# machcauH.net
KiCad netlist of a schematic drawn in Altium Designer
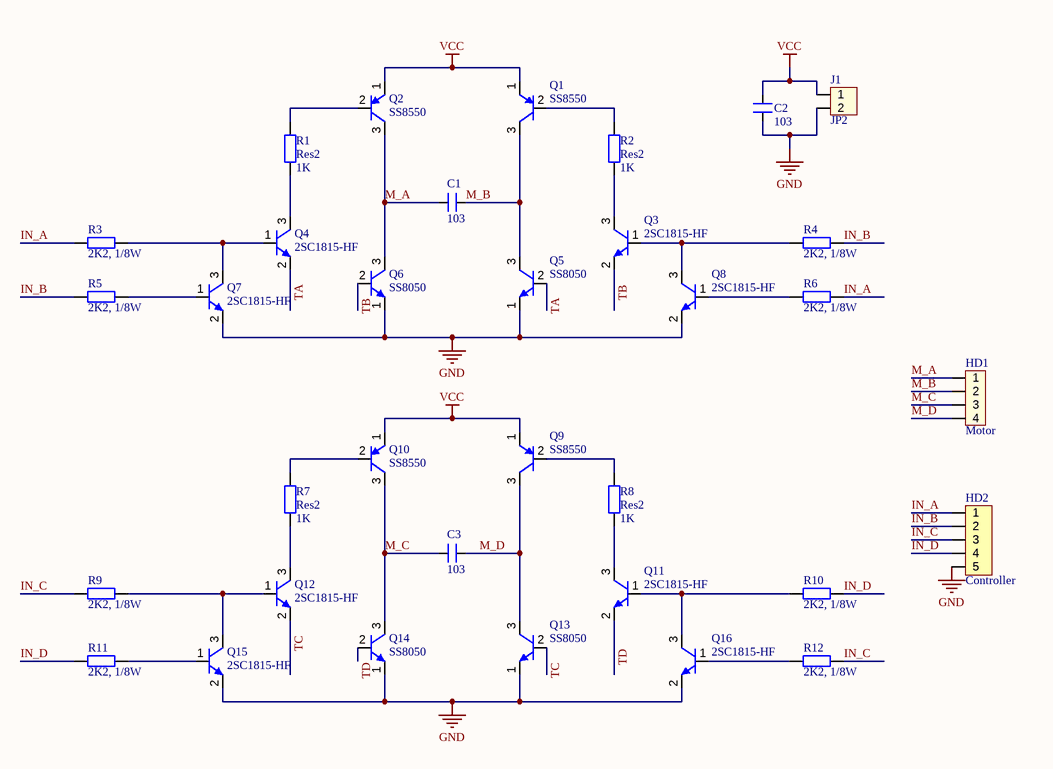
[diagram p0: machcauH.SchDoc]

(export (version "E")
  (design (tool "Eeschema 10.0.6"))
  (components
    (comp (ref "C1")
      (value "103")
      (footprint "CN1.5")
      (description "Cap np 682pF => 104pF")
      (libsource (lib "lpson") (part "CN1.5"))
    )
    (comp (ref "C2")
      (value "103")
      (footprint "CN1.5")
      (description "Cap np 682pF => 104pF")
      (libsource (lib "lpson") (part "CN1.5"))
    )
    (comp (ref "C3")
      (value "103")
      (footprint "CN1.5")
      (description "Cap np 682pF => 104pF")
      (libsource (lib "lpson") (part "CN1.5"))
    )
    (comp (ref "HD1")
      (value "Motor")
      (footprint "Header_4")
      (description "Header 4")
      (libsource (lib "lpson") (part "Header4"))
    )
    (comp (ref "HD2")
      (value "Controller")
      (footprint "HDR5")
      (description "Header IDC, 5 x 1 Pin Vertical 2.54mm Pitch (Non-Boxed, Male)")
      (fields
        (field (name "MANUFACTURER") "Würth Elektronik eiSos GmbH")
        (field (name "PARTNO") "613002143121")
        (field (name "CREATED BY") "Karrer Zheng")
      )
      (libsource (lib "My Library") (part "Header5"))
    )
    (comp (ref "J1")
      (value "JP2")
      (footprint "CON2")
      (description "Connector 2")
      (libsource (lib "lpson") (part "Con2"))
    )
    (comp (ref "Q1")
      (value "SS8550")
      (footprint "SS8550")
      (description "Trans PNP -25V -1.5A TO-92")
      (libsource (lib "lpson") (part "SS8550"))
    )
    (comp (ref "Q2")
      (value "SS8550")
      (footprint "SS8550")
      (description "Trans PNP -25V -1.5A TO-92")
      (libsource (lib "lpson") (part "SS8550"))
    )
    (comp (ref "Q3")
      (value "2SC1815-HF")
      (footprint "2SC1815-HF")
      (description "Trans NPN 50V 150mA SOT-23")
      (libsource (lib "lpson") (part "2SC1815-HF"))
    )
    (comp (ref "Q4")
      (value "2SC1815-HF")
      (footprint "2SC1815-HF")
      (description "Trans NPN 50V 150mA SOT-23")
      (libsource (lib "lpson") (part "2SC1815-HF"))
    )
    (comp (ref "Q5")
      (value "SS8050")
      (footprint "SS8050")
      (description "Trans NPN 25V 1.5A TO-92")
      (libsource (lib "lpson") (part "SS8050"))
    )
    (comp (ref "Q6")
      (value "SS8050")
      (footprint "SS8050")
      (description "Trans NPN 25V 1.5A TO-92")
      (libsource (lib "lpson") (part "SS8050"))
    )
    (comp (ref "Q7")
      (value "2SC1815-HF")
      (footprint "2SC1815-HF")
      (description "Trans NPN 50V 150mA SOT-23")
      (libsource (lib "lpson") (part "2SC1815-HF"))
    )
    (comp (ref "Q8")
      (value "2SC1815-HF")
      (footprint "2SC1815-HF")
      (description "Trans NPN 50V 150mA SOT-23")
      (libsource (lib "lpson") (part "2SC1815-HF"))
    )
    (comp (ref "Q9")
      (value "SS8550")
      (footprint "SS8550")
      (description "Trans PNP -25V -1.5A TO-92")
      (libsource (lib "lpson") (part "SS8550"))
    )
    (comp (ref "Q10")
      (value "SS8550")
      (footprint "SS8550")
      (description "Trans PNP -25V -1.5A TO-92")
      (libsource (lib "lpson") (part "SS8550"))
    )
    (comp (ref "Q11")
      (value "2SC1815-HF")
      (footprint "2SC1815-HF")
      (description "Trans NPN 50V 150mA SOT-23")
      (libsource (lib "lpson") (part "2SC1815-HF"))
    )
    (comp (ref "Q12")
      (value "2SC1815-HF")
      (footprint "2SC1815-HF")
      (description "Trans NPN 50V 150mA SOT-23")
      (libsource (lib "lpson") (part "2SC1815-HF"))
    )
    (comp (ref "Q13")
      (value "SS8050")
      (footprint "SS8050")
      (description "Trans NPN 25V 1.5A TO-92")
      (libsource (lib "lpson") (part "SS8050"))
    )
    (comp (ref "Q14")
      (value "SS8050")
      (footprint "SS8050")
      (description "Trans NPN 25V 1.5A TO-92")
      (libsource (lib "lpson") (part "SS8050"))
    )
    (comp (ref "Q15")
      (value "2SC1815-HF")
      (footprint "2SC1815-HF")
      (description "Trans NPN 50V 150mA SOT-23")
      (libsource (lib "lpson") (part "2SC1815-HF"))
    )
    (comp (ref "Q16")
      (value "2SC1815-HF")
      (footprint "2SC1815-HF")
      (description "Trans NPN 50V 150mA SOT-23")
      (libsource (lib "lpson") (part "2SC1815-HF"))
    )
    (comp (ref "R1")
      (value "Res2")
      (footprint "RES 1/4W CFR25")
      (description "Resistor")
      (fields (field (name "ALTIUM_VALUE") "1K") (field (name "PUBLISHER") "Altium Limited"))
      (libsource (lib "lpson") (part "Res2"))
    )
    (comp (ref "R2")
      (value "Res2")
      (footprint "RES 1/4W CFR25")
      (description "Resistor")
      (fields (field (name "ALTIUM_VALUE") "1K") (field (name "PUBLISHER") "Altium Limited"))
      (libsource (lib "lpson") (part "Res2"))
    )
    (comp (ref "R3")
      (value "2K2, 1/8W")
      (footprint "DIEN TRO 0805")
      (description "Resistor SMD 0603")
      (fields (field (name "Comment") "R0603") (field (name "PUBLISHER") "Altium Limited"))
      (libsource (lib "My Library") (part "R0603"))
    )
    (comp (ref "R4")
      (value "2K2, 1/8W")
      (footprint "DIEN TRO 0805")
      (description "Resistor SMD 0603")
      (fields (field (name "Comment") "R0603") (field (name "PUBLISHER") "Altium Limited"))
      (libsource (lib "My Library") (part "R0603"))
    )
    (comp (ref "R5")
      (value "2K2, 1/8W")
      (footprint "DIEN TRO 0805")
      (description "Resistor SMD 0603")
      (fields (field (name "Comment") "R0603") (field (name "PUBLISHER") "Altium Limited"))
      (libsource (lib "My Library") (part "R0603"))
    )
    (comp (ref "R6")
      (value "2K2, 1/8W")
      (footprint "DIEN TRO 0805")
      (description "Resistor SMD 0603")
      (fields (field (name "Comment") "R0603") (field (name "PUBLISHER") "Altium Limited"))
      (libsource (lib "My Library") (part "R0603"))
    )
    (comp (ref "R7")
      (value "Res2")
      (footprint "RES 1/4W CFR25")
      (description "Resistor")
      (fields (field (name "ALTIUM_VALUE") "1K") (field (name "PUBLISHER") "Altium Limited"))
      (libsource (lib "lpson") (part "Res2"))
    )
    (comp (ref "R8")
      (value "Res2")
      (footprint "RES 1/4W CFR25")
      (description "Resistor")
      (fields (field (name "ALTIUM_VALUE") "1K") (field (name "PUBLISHER") "Altium Limited"))
      (libsource (lib "lpson") (part "Res2"))
    )
    (comp (ref "R9")
      (value "2K2, 1/8W")
      (footprint "DIEN TRO 0805")
      (description "Resistor SMD 0603")
      (fields (field (name "Comment") "R0603") (field (name "PUBLISHER") "Altium Limited"))
      (libsource (lib "My Library") (part "R0603"))
    )
    (comp (ref "R10")
      (value "2K2, 1/8W")
      (footprint "DIEN TRO 0805")
      (description "Resistor SMD 0603")
      (fields (field (name "Comment") "R0603") (field (name "PUBLISHER") "Altium Limited"))
      (libsource (lib "My Library") (part "R0603"))
    )
    (comp (ref "R11")
      (value "2K2, 1/8W")
      (footprint "DIEN TRO 0805")
      (description "Resistor SMD 0603")
      (fields (field (name "Comment") "R0603") (field (name "PUBLISHER") "Altium Limited"))
      (libsource (lib "My Library") (part "R0603"))
    )
    (comp (ref "R12")
      (value "2K2, 1/8W")
      (footprint "DIEN TRO 0805")
      (description "Resistor SMD 0603")
      (fields (field (name "Comment") "R0603") (field (name "PUBLISHER") "Altium Limited"))
      (libsource (lib "My Library") (part "R0603"))
    )
  )
  (nets
    (net (code "1") (name "/IN_A") (class "Default")
      (node (ref "HD2") (pin "1") (pinfunction "1_1") (pintype "passive"))
      (node (ref "R3") (pin "1") (pinfunction "1_1") (pintype "passive"))
      (node (ref "R6") (pin "2") (pinfunction "2_2") (pintype "passive"))
    )
    (net (code "2") (name "/IN_B") (class "Default")
      (node (ref "HD2") (pin "2") (pinfunction "2_2") (pintype "passive"))
      (node (ref "R4") (pin "2") (pinfunction "2_2") (pintype "passive"))
      (node (ref "R5") (pin "1") (pinfunction "1_1") (pintype "passive"))
    )
    (net (code "3") (name "/IN_C") (class "Default")
      (node (ref "HD2") (pin "3") (pinfunction "3_3") (pintype "passive"))
      (node (ref "R12") (pin "2") (pinfunction "2_2") (pintype "passive"))
      (node (ref "R9") (pin "1") (pinfunction "1_1") (pintype "passive"))
    )
    (net (code "4") (name "/IN_D") (class "Default")
      (node (ref "HD2") (pin "4") (pinfunction "4_4") (pintype "passive"))
      (node (ref "R10") (pin "2") (pinfunction "2_2") (pintype "passive"))
      (node (ref "R11") (pin "1") (pinfunction "1_1") (pintype "passive"))
    )
    (net (code "5") (name "/M_A") (class "Default")
      (node (ref "C1") (pin "1") (pinfunction "1_1") (pintype "passive"))
      (node (ref "HD1") (pin "1") (pinfunction "1_1") (pintype "passive"))
      (node (ref "Q2") (pin "3") (pinfunction "C_3") (pintype "passive"))
      (node (ref "Q6") (pin "3") (pinfunction "C_3") (pintype "passive"))
    )
    (net (code "6") (name "/M_B") (class "Default")
      (node (ref "C1") (pin "2") (pinfunction "2_2") (pintype "passive"))
      (node (ref "HD1") (pin "2") (pinfunction "2_2") (pintype "passive"))
      (node (ref "Q1") (pin "3") (pinfunction "C_3") (pintype "passive"))
      (node (ref "Q5") (pin "3") (pinfunction "C_3") (pintype "passive"))
    )
    (net (code "7") (name "/M_C") (class "Default")
      (node (ref "C3") (pin "2") (pinfunction "2_2") (pintype "passive"))
      (node (ref "HD1") (pin "3") (pinfunction "3_3") (pintype "passive"))
      (node (ref "Q10") (pin "3") (pinfunction "C_3") (pintype "passive"))
      (node (ref "Q14") (pin "3") (pinfunction "C_3") (pintype "passive"))
    )
    (net (code "8") (name "/M_D") (class "Default")
      (node (ref "C3") (pin "1") (pinfunction "1_1") (pintype "passive"))
      (node (ref "HD1") (pin "4") (pinfunction "4_4") (pintype "passive"))
      (node (ref "Q13") (pin "3") (pinfunction "C_3") (pintype "passive"))
      (node (ref "Q9") (pin "3") (pinfunction "C_3") (pintype "passive"))
    )
    (net (code "9") (name "/TA") (class "Default")
      (node (ref "Q4") (pin "2") (pinfunction "E_2") (pintype "passive"))
      (node (ref "Q5") (pin "2") (pinfunction "B_2") (pintype "passive"))
    )
    (net (code "10") (name "/TB") (class "Default")
      (node (ref "Q3") (pin "2") (pinfunction "E_2") (pintype "passive"))
      (node (ref "Q6") (pin "2") (pinfunction "B_2") (pintype "passive"))
    )
    (net (code "11") (name "/TC") (class "Default")
      (node (ref "Q12") (pin "2") (pinfunction "E_2") (pintype "passive"))
      (node (ref "Q13") (pin "2") (pinfunction "B_2") (pintype "passive"))
    )
    (net (code "12") (name "/TD") (class "Default")
      (node (ref "Q11") (pin "2") (pinfunction "E_2") (pintype "passive"))
      (node (ref "Q14") (pin "2") (pinfunction "B_2") (pintype "passive"))
    )
    (net (code "13") (name "GND") (class "Default")
      (node (ref "C2") (pin "1") (pinfunction "1_1") (pintype "passive"))
      (node (ref "HD2") (pin "5") (pinfunction "5_5") (pintype "passive"))
      (node (ref "J1") (pin "2") (pinfunction "2_2") (pintype "passive"))
      (node (ref "Q13") (pin "1") (pinfunction "E_1") (pintype "passive"))
      (node (ref "Q14") (pin "1") (pinfunction "E_1") (pintype "passive"))
      (node (ref "Q15") (pin "2") (pinfunction "E_2") (pintype "passive"))
      (node (ref "Q16") (pin "2") (pinfunction "E_2") (pintype "passive"))
      (node (ref "Q5") (pin "1") (pinfunction "E_1") (pintype "passive"))
      (node (ref "Q6") (pin "1") (pinfunction "E_1") (pintype "passive"))
      (node (ref "Q7") (pin "2") (pinfunction "E_2") (pintype "passive"))
      (node (ref "Q8") (pin "2") (pinfunction "E_2") (pintype "passive"))
    )
    (net (code "14") (name "Net-(Q1-B)") (class "Default")
      (node (ref "Q1") (pin "2") (pinfunction "B_2") (pintype "passive"))
      (node (ref "R2") (pin "2") (pinfunction "2_2") (pintype "passive"))
    )
    (net (code "15") (name "Net-(Q2-B)") (class "Default")
      (node (ref "Q2") (pin "2") (pinfunction "B_2") (pintype "passive"))
      (node (ref "R1") (pin "2") (pinfunction "2_2") (pintype "passive"))
    )
    (net (code "16") (name "Net-(Q3-B)") (class "Default")
      (node (ref "Q3") (pin "1") (pinfunction "B_1") (pintype "passive"))
      (node (ref "Q8") (pin "3") (pinfunction "C_3") (pintype "passive"))
      (node (ref "R4") (pin "1") (pinfunction "1_1") (pintype "passive"))
    )
    (net (code "17") (name "Net-(Q3-C)") (class "Default")
      (node (ref "Q3") (pin "3") (pinfunction "C_3") (pintype "passive"))
      (node (ref "R2") (pin "1") (pinfunction "1_1") (pintype "passive"))
    )
    (net (code "18") (name "Net-(Q4-B)") (class "Default")
      (node (ref "Q4") (pin "1") (pinfunction "B_1") (pintype "passive"))
      (node (ref "Q7") (pin "3") (pinfunction "C_3") (pintype "passive"))
      (node (ref "R3") (pin "2") (pinfunction "2_2") (pintype "passive"))
    )
    (net (code "19") (name "Net-(Q4-C)") (class "Default")
      (node (ref "Q4") (pin "3") (pinfunction "C_3") (pintype "passive"))
      (node (ref "R1") (pin "1") (pinfunction "1_1") (pintype "passive"))
    )
    (net (code "20") (name "Net-(Q7-B)") (class "Default")
      (node (ref "Q7") (pin "1") (pinfunction "B_1") (pintype "passive"))
      (node (ref "R5") (pin "2") (pinfunction "2_2") (pintype "passive"))
    )
    (net (code "21") (name "Net-(Q8-B)") (class "Default")
      (node (ref "Q8") (pin "1") (pinfunction "B_1") (pintype "passive"))
      (node (ref "R6") (pin "1") (pinfunction "1_1") (pintype "passive"))
    )
    (net (code "22") (name "Net-(Q9-B)") (class "Default")
      (node (ref "Q9") (pin "2") (pinfunction "B_2") (pintype "passive"))
      (node (ref "R8") (pin "2") (pinfunction "2_2") (pintype "passive"))
    )
    (net (code "23") (name "Net-(Q10-B)") (class "Default")
      (node (ref "Q10") (pin "2") (pinfunction "B_2") (pintype "passive"))
      (node (ref "R7") (pin "2") (pinfunction "2_2") (pintype "passive"))
    )
    (net (code "24") (name "Net-(Q11-B)") (class "Default")
      (node (ref "Q11") (pin "1") (pinfunction "B_1") (pintype "passive"))
      (node (ref "Q16") (pin "3") (pinfunction "C_3") (pintype "passive"))
      (node (ref "R10") (pin "1") (pinfunction "1_1") (pintype "passive"))
    )
    (net (code "25") (name "Net-(Q11-C)") (class "Default")
      (node (ref "Q11") (pin "3") (pinfunction "C_3") (pintype "passive"))
      (node (ref "R8") (pin "1") (pinfunction "1_1") (pintype "passive"))
    )
    (net (code "26") (name "Net-(Q12-B)") (class "Default")
      (node (ref "Q12") (pin "1") (pinfunction "B_1") (pintype "passive"))
      (node (ref "Q15") (pin "3") (pinfunction "C_3") (pintype "passive"))
      (node (ref "R9") (pin "2") (pinfunction "2_2") (pintype "passive"))
    )
    (net (code "27") (name "Net-(Q12-C)") (class "Default")
      (node (ref "Q12") (pin "3") (pinfunction "C_3") (pintype "passive"))
      (node (ref "R7") (pin "1") (pinfunction "1_1") (pintype "passive"))
    )
    (net (code "28") (name "Net-(Q15-B)") (class "Default")
      (node (ref "Q15") (pin "1") (pinfunction "B_1") (pintype "passive"))
      (node (ref "R11") (pin "2") (pinfunction "2_2") (pintype "passive"))
    )
    (net (code "29") (name "Net-(Q16-B)") (class "Default")
      (node (ref "Q16") (pin "1") (pinfunction "B_1") (pintype "passive"))
      (node (ref "R12") (pin "1") (pinfunction "1_1") (pintype "passive"))
    )
    (net (code "30") (name "VCC") (class "Default")
      (node (ref "C2") (pin "2") (pinfunction "2_2") (pintype "passive"))
      (node (ref "J1") (pin "1") (pinfunction "1_1") (pintype "passive"))
      (node (ref "Q1") (pin "1") (pinfunction "E_1") (pintype "passive"))
      (node (ref "Q10") (pin "1") (pinfunction "E_1") (pintype "passive"))
      (node (ref "Q2") (pin "1") (pinfunction "E_1") (pintype "passive"))
      (node (ref "Q9") (pin "1") (pinfunction "E_1") (pintype "passive"))
    )
  )
)
